# SensorStick.net
KiCad netlist of a schematic drawn in EAGLE
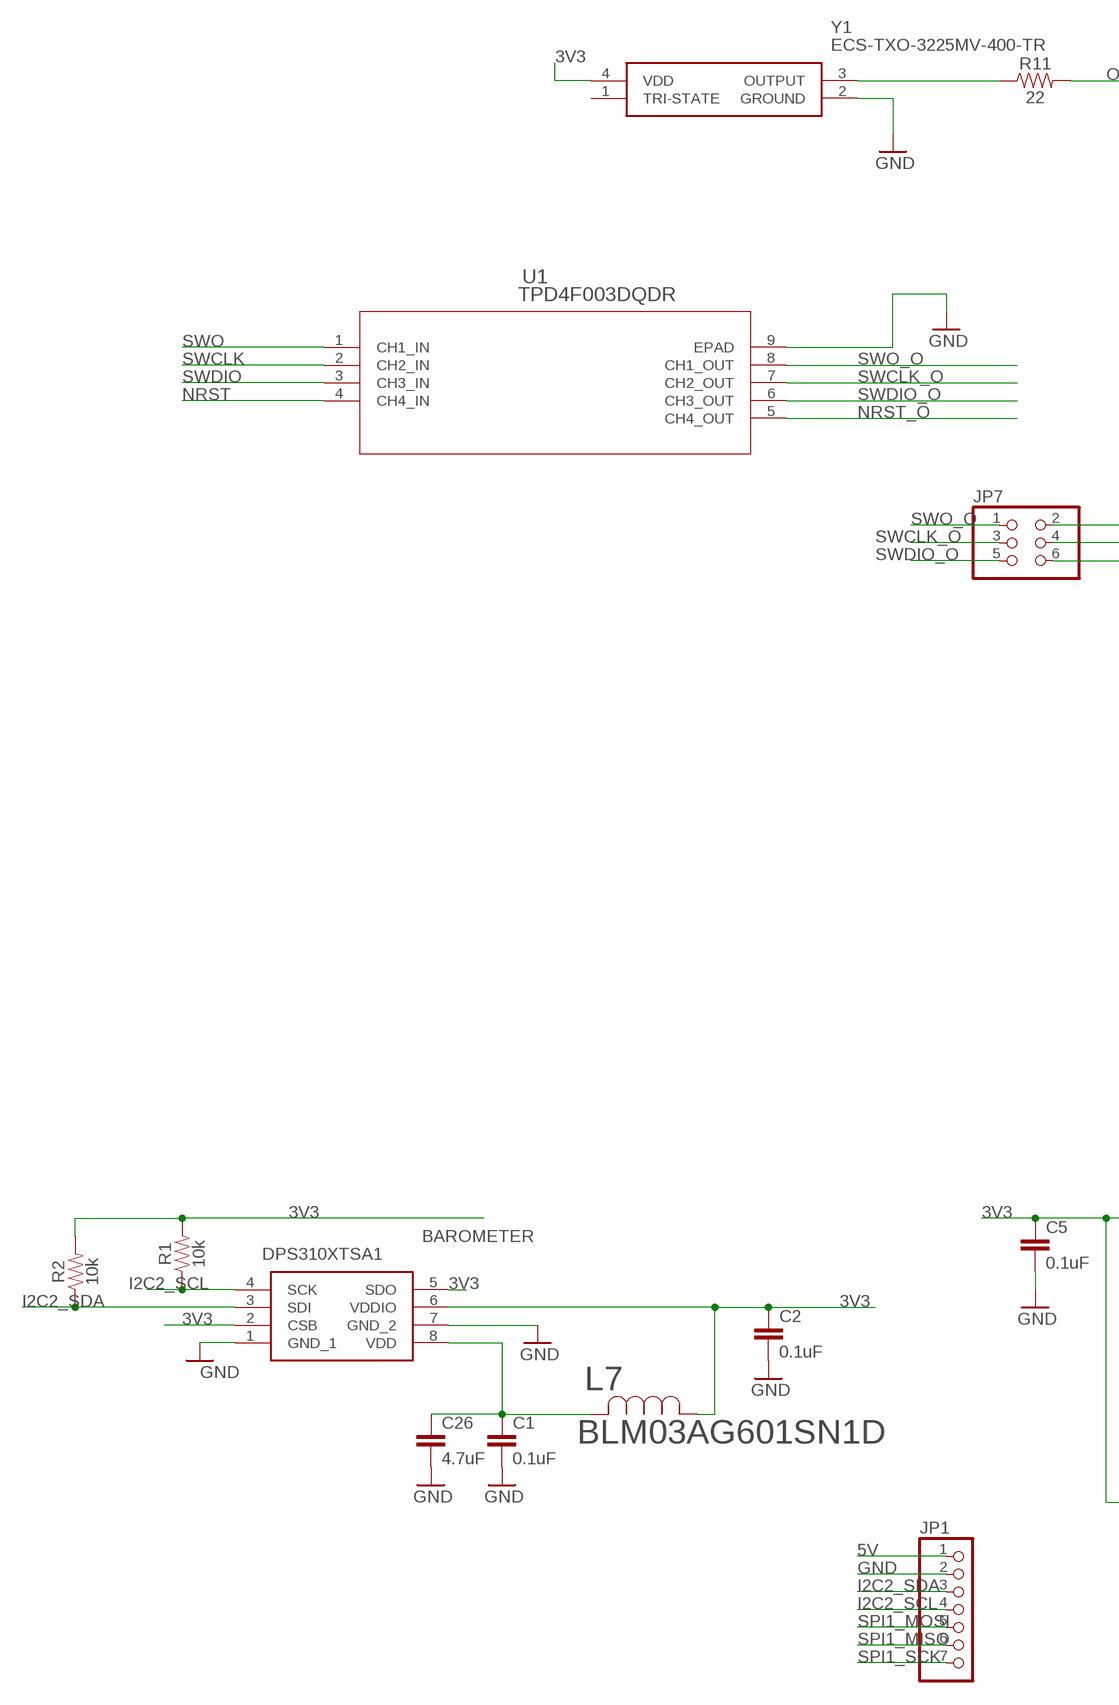
[diagram p0: schematic, sheet 1, part 1 of 2]
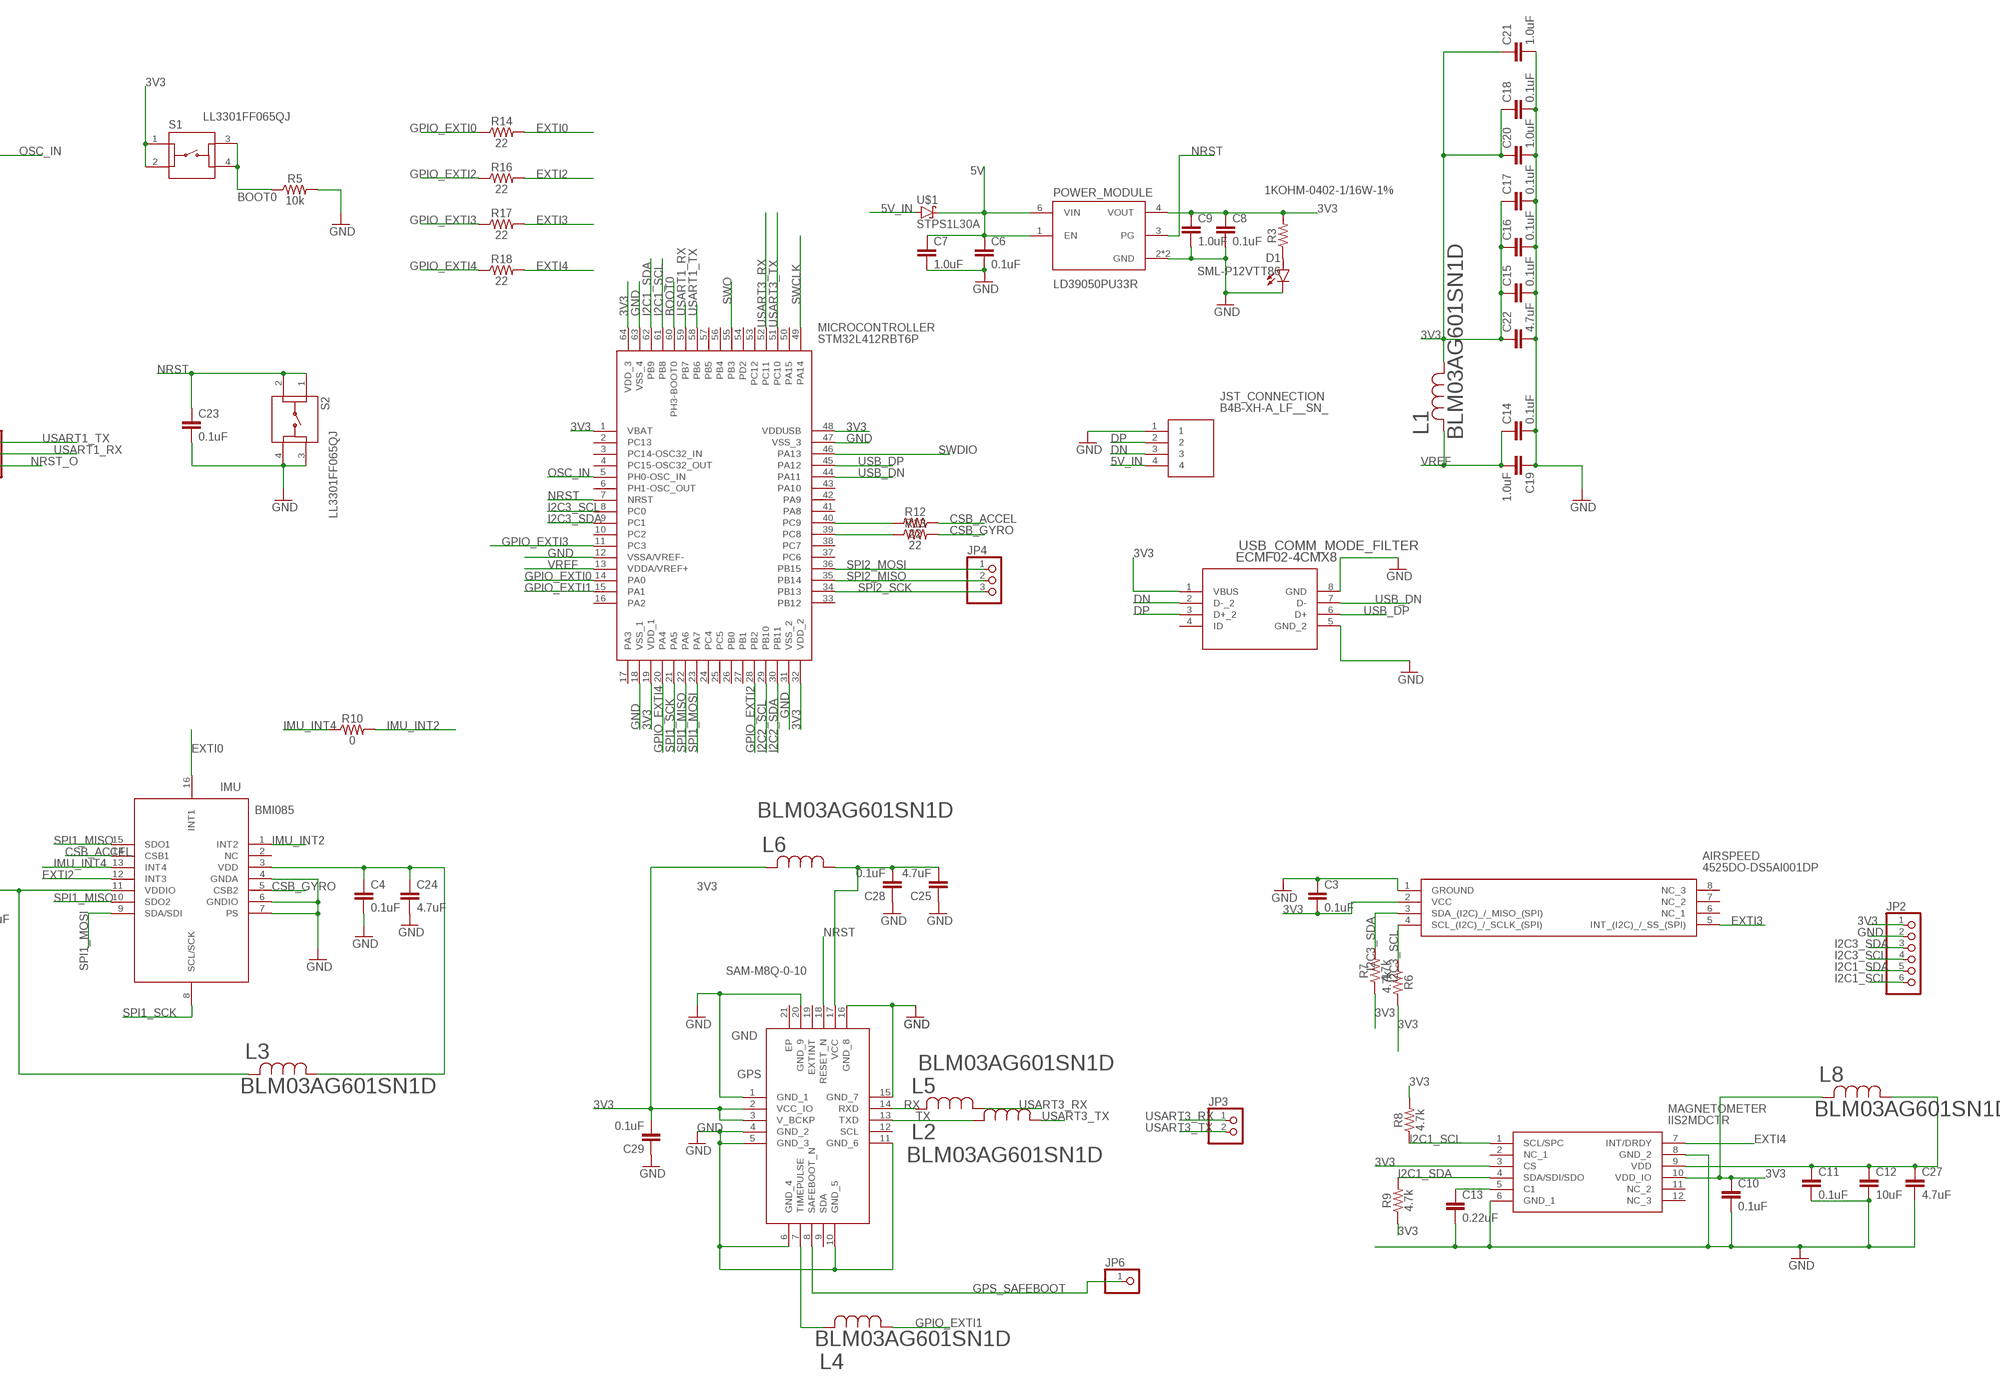
[diagram p1: schematic, sheet 1, part 2 of 2]

(export (version "E")
  (design (tool "Eeschema 10.0.6"))
  (components
    (comp (ref "AIRSPEED")
      (value "4525DO-DS5AI001DP")
      (footprint "eagle-import:4525DO-DS...P")
      (fields (field (name "MOUSER_PART_NUMBER") "824-4525DODS5AI001DP"))
      (libsource (lib "eagle-import") (part "4525DO-DS5AI001DP"))
    )
    (comp (ref "BAROMETER")
      (value "DPS310XTSA1")
      (footprint "eagle-import:DPS310XTSA1")
      (fields (field (name "MOUSER_PART_NUMBER") "726-DPS310XTSA1"))
      (libsource (lib "eagle-import") (part "DPS310XTSA1"))
    )
    (comp (ref "C1")
      (value "0.1uF")
      (footprint "eagle-import:0402")
      (libsource (lib "eagle-import") (part "0.1UF-0402-6.3V-10%-X7R"))
    )
    (comp (ref "C2")
      (value "0.1uF")
      (footprint "eagle-import:0402")
      (libsource (lib "eagle-import") (part "0.1UF-0402-6.3V-10%-X7R"))
    )
    (comp (ref "C3")
      (value "0.1uF")
      (footprint "eagle-import:0402")
      (fields (field (name "SPICEPREFIX") "C"))
      (libsource (lib "eagle-import") (part "0.1UF-0402-6.3V-10%-X7R"))
    )
    (comp (ref "C4")
      (value "0.1uF")
      (footprint "eagle-import:0402")
      (libsource (lib "eagle-import") (part "0.1UF-0402-6.3V-10%-X7R"))
    )
    (comp (ref "C5")
      (value "0.1uF")
      (footprint "eagle-import:0402")
      (libsource (lib "eagle-import") (part "0.1UF-0402-6.3V-10%-X7R"))
    )
    (comp (ref "C6")
      (value "0.1uF")
      (footprint "eagle-import:0402")
      (libsource (lib "eagle-import") (part "0.1UF-0402-6.3V-10%-X7R"))
    )
    (comp (ref "C7")
      (value "1.0uF")
      (footprint "eagle-import:0402")
      (libsource (lib "eagle-import") (part "1.0UF-0402-16V-10%"))
    )
    (comp (ref "C8")
      (value "0.1uF")
      (footprint "eagle-import:0402")
      (libsource (lib "eagle-import") (part "0.1UF-0402-6.3V-10%-X7R"))
    )
    (comp (ref "C9")
      (value "1.0uF")
      (footprint "eagle-import:0402")
      (libsource (lib "eagle-import") (part "1.0UF-0402-16V-10%"))
    )
    (comp (ref "C10")
      (value "0.1uF")
      (footprint "eagle-import:0402")
      (libsource (lib "eagle-import") (part "0.1UF-0402-6.3V-10%-X7R"))
    )
    (comp (ref "C11")
      (value "0.1uF")
      (footprint "eagle-import:0402")
      (libsource (lib "eagle-import") (part "0.1UF-0402-6.3V-10%-X7R"))
    )
    (comp (ref "C12")
      (value "10uF")
      (footprint "eagle-import:0603")
      (libsource (lib "eagle-import") (part "10UF-0603-6.3V-20%"))
    )
    (comp (ref "C13")
      (value "0.22uF")
      (footprint "eagle-import:0603")
      (libsource (lib "eagle-import") (part "0.22UF-0603-25V-10%"))
    )
    (comp (ref "C14")
      (value "0.1uF")
      (footprint "eagle-import:0603")
      (libsource (lib "eagle-import") (part "SparkFun-Capacitors_510_0.1UF-0603-25V-5%"))
    )
    (comp (ref "C15")
      (value "0.1uF")
      (footprint "eagle-import:0603")
      (libsource (lib "eagle-import") (part "SparkFun-Capacitors_510_0.1UF-0603-25V-5%"))
    )
    (comp (ref "C16")
      (value "0.1uF")
      (footprint "eagle-import:0603")
      (libsource (lib "eagle-import") (part "SparkFun-Capacitors_510_0.1UF-0603-25V-5%"))
    )
    (comp (ref "C17")
      (value "0.1uF")
      (footprint "eagle-import:0603")
      (libsource (lib "eagle-import") (part "SparkFun-Capacitors_510_0.1UF-0603-25V-5%"))
    )
    (comp (ref "C18")
      (value "0.1uF")
      (footprint "eagle-import:0603")
      (libsource (lib "eagle-import") (part "SparkFun-Capacitors_510_0.1UF-0603-25V-5%"))
    )
    (comp (ref "C19")
      (value "1.0uF")
      (footprint "eagle-import:0805")
      (libsource (lib "eagle-import") (part "SparkFun-Capacitors_510_1.0UF-0805-25V-10%"))
    )
    (comp (ref "C20")
      (value "1.0uF")
      (footprint "eagle-import:0805")
      (libsource (lib "eagle-import") (part "SparkFun-Capacitors_510_1.0UF-0805-25V-10%"))
    )
    (comp (ref "C21")
      (value "1.0uF")
      (footprint "eagle-import:0805")
      (libsource (lib "eagle-import") (part "SparkFun-Capacitors_510_1.0UF-0805-25V-10%"))
    )
    (comp (ref "C22")
      (value "4.7uF")
      (footprint "eagle-import:0603")
      (libsource (lib "eagle-import") (part "4.7UF0603"))
    )
    (comp (ref "C23")
      (value "0.1uF")
      (footprint "eagle-import:0603")
      (libsource (lib "eagle-import") (part "SparkFun-Capacitors_510_0.1UF-0603-25V-5%"))
    )
    (comp (ref "C24")
      (value "4.7uF")
      (footprint "eagle-import:0603")
      (libsource (lib "eagle-import") (part "4.7UF0603"))
    )
    (comp (ref "C25")
      (value "4.7uF")
      (footprint "eagle-import:0603")
      (libsource (lib "eagle-import") (part "4.7UF0603"))
    )
    (comp (ref "C26")
      (value "4.7uF")
      (footprint "eagle-import:0603")
      (libsource (lib "eagle-import") (part "4.7UF0603"))
    )
    (comp (ref "C27")
      (value "4.7uF")
      (footprint "eagle-import:0603")
      (libsource (lib "eagle-import") (part "4.7UF0603"))
    )
    (comp (ref "C28")
      (value "0.1uF")
      (footprint "eagle-import:0402")
      (libsource (lib "eagle-import") (part "SparkFun-Capacitors_510_0.1UF-0402-16V-10%"))
    )
    (comp (ref "C29")
      (value "0.1uF")
      (footprint "eagle-import:0402")
      (libsource (lib "eagle-import") (part "SparkFun-Capacitors_510_0.1UF-0402-16V-10%"))
    )
    (comp (ref "D1")
      (value "SML-P12VTT86")
      (footprint "eagle-import:LED_SML-P11UTT86R")
      (fields (field (name "MF") "Rohm"))
      (libsource (lib "eagle-import") (part "SML-P12VTT86"))
    )
    (comp (ref "GPS")
      (value "SAM-M8Q-0-10")
      (footprint "eagle-import:SAMM8Q010")
      (libsource (lib "eagle-import") (part "SAM-M8Q-0-10"))
    )
    (comp (ref "IMU")
      (value "BMI085")
      (footprint "eagle-import:BMI085")
      (fields (field (name "MOUSER_PART_NUMBER") "262-BMI085"))
      (libsource (lib "eagle-import") (part "BMI085"))
    )
    (comp (ref "JP1")
      (value "PINHD-1X7")
      (footprint "eagle-import:1X07")
      (libsource (lib "eagle-import") (part "PINHD-1X7"))
    )
    (comp (ref "JP2")
      (value "PINHD-1X6")
      (footprint "eagle-import:1X06")
      (libsource (lib "eagle-import") (part "PINHD-1X6"))
    )
    (comp (ref "JP3")
      (value "PINHD-1X2")
      (footprint "eagle-import:1X02")
      (libsource (lib "eagle-import") (part "PINHD-1X2"))
    )
    (comp (ref "JP4")
      (value "PINHD-1X3")
      (footprint "eagle-import:1X03")
      (libsource (lib "eagle-import") (part "PINHD-1X3"))
    )
    (comp (ref "JP6")
      (value "PINHD-1X1")
      (footprint "eagle-import:1X01")
      (libsource (lib "eagle-import") (part "PINHD-1X1"))
    )
    (comp (ref "JP7")
      (value "PINHD-2X3")
      (footprint "eagle-import:2X03")
      (libsource (lib "eagle-import") (part "PINHD-2X3"))
    )
    (comp (ref "JST_CONNECTION")
      (value "B4B-XH-A_LF__SN_")
      (footprint "eagle-import:B4BXHALFSN")
      (fields (field (name "ARROW_PART_NUMBER") "B4B-XH-A(LF)(SN)"))
      (libsource (lib "eagle-import") (part "B4B-XH-A_LF__SN_"))
    )
    (comp (ref "L1")
      (value "BLM03AG601SN1D")
      (footprint "eagle-import:IND_BLM03_0201_MUR")
      (fields (field (name "COPYRIGHT") "Copyright (C) 2023 Ultra Librarian. All rights reserved."))
      (libsource (lib "eagle-import") (part "BLM03AG601SN1D"))
    )
    (comp (ref "L2")
      (value "BLM03AG601SN1D")
      (footprint "eagle-import:IND_BLM03_0201_MUR")
      (fields (field (name "COPYRIGHT") "Copyright (C) 2023 Ultra Librarian. All rights reserved."))
      (libsource (lib "eagle-import") (part "BLM03AG601SN1D"))
    )
    (comp (ref "L3")
      (value "BLM03AG601SN1D")
      (footprint "eagle-import:IND_BLM03_0201_MUR")
      (fields (field (name "COPYRIGHT") "Copyright (C) 2023 Ultra Librarian. All rights reserved."))
      (libsource (lib "eagle-import") (part "BLM03AG601SN1D"))
    )
    (comp (ref "L4")
      (value "BLM03AG601SN1D")
      (footprint "eagle-import:IND_BLM03_0201_MUR")
      (fields (field (name "COPYRIGHT") "Copyright (C) 2023 Ultra Librarian. All rights reserved."))
      (libsource (lib "eagle-import") (part "BLM03AG601SN1D"))
    )
    (comp (ref "L5")
      (value "BLM03AG601SN1D")
      (footprint "eagle-import:IND_BLM03_0201_MUR")
      (fields (field (name "COPYRIGHT") "Copyright (C) 2023 Ultra Librarian. All rights reserved."))
      (libsource (lib "eagle-import") (part "BLM03AG601SN1D"))
    )
    (comp (ref "L6")
      (value "BLM03AG601SN1D")
      (footprint "eagle-import:IND_BLM03_0201_MUR")
      (fields (field (name "COPYRIGHT") "Copyright (C) 2023 Ultra Librarian. All rights reserved."))
      (libsource (lib "eagle-import") (part "BLM03AG601SN1D"))
    )
    (comp (ref "L7")
      (value "BLM03AG601SN1D")
      (footprint "eagle-import:IND_BLM03_0201_MUR")
      (fields (field (name "COPYRIGHT") "Copyright (C) 2023 Ultra Librarian. All rights reserved."))
      (libsource (lib "eagle-import") (part "BLM03AG601SN1D"))
    )
    (comp (ref "L8")
      (value "BLM03AG601SN1D")
      (footprint "eagle-import:IND_BLM03_0201_MUR")
      (fields (field (name "COPYRIGHT") "Copyright (C) 2023 Ultra Librarian. All rights reserved."))
      (libsource (lib "eagle-import") (part "BLM03AG601SN1D"))
    )
    (comp (ref "MAGNETOMETER")
      (value "IIS2MDCTR")
      (footprint "eagle-import:IIS2MDCTR")
      (fields (field (name "MOUSER_PART_NUMBER") "511-IIS2MDCTR"))
      (libsource (lib "eagle-import") (part "IIS2MDCTR"))
    )
    (comp (ref "MICROCONTROLLER")
      (value "STM32L412RBT6P")
      (footprint "eagle-import:QFP50P1200X1200X160-64N")
      (fields (field (name "MOUSER_PART_NUMBER") "511-STM32L412RBT6P"))
      (libsource (lib "eagle-import") (part "STM32L412RBT6P"))
    )
    (comp (ref "POWER_MODULE")
      (value "LD39050PU33R")
      (footprint "eagle-import:SON95P300X300X100-7N")
      (fields (field (name "MF") "STMicroelectronics"))
      (libsource (lib "eagle-import") (part "LD39050PU33R"))
    )
    (comp (ref "R1")
      (value "10k")
      (footprint "eagle-import:0402")
      (libsource (lib "eagle-import") (part "10KOHM-0402-1/16W-1%"))
    )
    (comp (ref "R2")
      (value "10k")
      (footprint "eagle-import:0402")
      (libsource (lib "eagle-import") (part "10KOHM-0402-1/16W-1%"))
    )
    (comp (ref "R3")
      (value "1KOHM-0402-1/16W-1%")
      (footprint "eagle-import:0402")
      (libsource (lib "eagle-import") (part "1KOHM-0402-1/16W-1%"))
    )
    (comp (ref "R5")
      (value "10k")
      (footprint "eagle-import:0603")
      (libsource (lib "eagle-import") (part "SparkFun-Resistors_532_10KOHM-0603-1/10W-1%"))
    )
    (comp (ref "R6")
      (value "4.7k")
      (footprint "eagle-import:0603")
      (libsource (lib "eagle-import") (part "4.7KOHM-0603-1/10W-1%"))
    )
    (comp (ref "R7")
      (value "4.7k")
      (footprint "eagle-import:0603")
      (libsource (lib "eagle-import") (part "4.7KOHM-0603-1/10W-1%"))
    )
    (comp (ref "R8")
      (value "4.7k")
      (footprint "eagle-import:0603")
      (libsource (lib "eagle-import") (part "4.7KOHM-0603-1/10W-1%"))
    )
    (comp (ref "R9")
      (value "4.7k")
      (footprint "eagle-import:0603")
      (libsource (lib "eagle-import") (part "4.7KOHM-0603-1/10W-1%"))
    )
    (comp (ref "R10")
      (value "0")
      (footprint "eagle-import:0603")
      (libsource (lib "eagle-import") (part "0OHM-0603-1/10W-5%"))
    )
    (comp (ref "R11")
      (value "22")
      (footprint "eagle-import:0402")
      (libsource (lib "eagle-import") (part "22OHM-0402-1/10W-1%"))
    )
    (comp (ref "R12")
      (value "22")
      (footprint "eagle-import:0402")
      (libsource (lib "eagle-import") (part "22OHM-0402-1/10W-1%"))
    )
    (comp (ref "R13")
      (value "22")
      (footprint "eagle-import:0402")
      (libsource (lib "eagle-import") (part "22OHM-0402-1/10W-1%"))
    )
    (comp (ref "R14")
      (value "22")
      (footprint "eagle-import:0402")
      (libsource (lib "eagle-import") (part "22OHM-0402-1/10W-1%"))
    )
    (comp (ref "R16")
      (value "22")
      (footprint "eagle-import:0402")
      (libsource (lib "eagle-import") (part "22OHM-0402-1/10W-1%"))
    )
    (comp (ref "R17")
      (value "22")
      (footprint "eagle-import:0402")
      (libsource (lib "eagle-import") (part "22OHM-0402-1/10W-1%"))
    )
    (comp (ref "R18")
      (value "22")
      (footprint "eagle-import:0402")
      (libsource (lib "eagle-import") (part "22OHM-0402-1/10W-1%"))
    )
    (comp (ref "S1")
      (value "LL3301FF065QJ")
      (footprint "eagle-import:LL3301FF065QJ")
      (fields (field (name "MOUSER_PART_NUMBER") "612-LL3301FF065QJ"))
      (libsource (lib "eagle-import") (part "LL3301FF065QJ"))
    )
    (comp (ref "S2")
      (value "LL3301FF065QJ")
      (footprint "eagle-import:LL3301FF065QJ")
      (fields (field (name "MOUSER_PART_NUMBER") "612-LL3301FF065QJ"))
      (libsource (lib "eagle-import") (part "LL3301FF065QJ"))
    )
    (comp (ref "U$1")
      (value "STPS1L30A")
      (footprint "eagle-import:DIOM5226X223N")
      (libsource (lib "eagle-import") (part "STPS1L30A"))
    )
    (comp (ref "U1")
      (value "TPD4F003DQDR")
      (footprint "eagle-import:DQD8_1P2X0P4")
      (fields (field (name "COPYRIGHT") "Copyright (C) 2023 Ultra Librarian. All rights reserved."))
      (libsource (lib "eagle-import") (part "TPD4F003DQDR"))
    )
    (comp (ref "USB_COMM_MODE_FILTER")
      (value "ECMF02-4CMX8")
      (footprint "eagle-import:MICRO_QFN-8L_STM")
      (fields (field (name "COPYRIGHT") "Copyright (C) 2023 Ultra Librarian. All rights reserved."))
      (libsource (lib "eagle-import") (part "ECMF02-4CMX8"))
    )
    (comp (ref "Y1")
      (value "ECS-TXO-3225MV-400-TR")
      (footprint "eagle-import:ECSTXO3225MV400TR")
      (libsource (lib "eagle-import") (part "ECS-TXO-3225MV-400-TR"))
    )
  )
  (nets
    (net (code "1") (name "/3V3") (class "Default")
      (node (ref "AIRSPEED") (pin "2") (pinfunction "VCC_2") (pintype "power_in"))
      (node (ref "BAROMETER") (pin "2") (pinfunction "CSB_2") (pintype "bidirectional"))
      (node (ref "BAROMETER") (pin "5") (pinfunction "SDO_5") (pintype "bidirectional"))
      (node (ref "BAROMETER") (pin "6") (pinfunction "VDDIO_6") (pintype "bidirectional"))
      (node (ref "C10") (pin "1") (pinfunction "1_1") (pintype "passive"))
      (node (ref "C15") (pin "1") (pinfunction "1_1") (pintype "passive"))
      (node (ref "C16") (pin "1") (pinfunction "1_1") (pintype "passive"))
      (node (ref "C17") (pin "1") (pinfunction "1_1") (pintype "passive"))
      (node (ref "C18") (pin "1") (pinfunction "1_1") (pintype "passive"))
      (node (ref "C2") (pin "1") (pinfunction "1_1") (pintype "passive"))
      (node (ref "C20") (pin "1") (pinfunction "1_1") (pintype "passive"))
      (node (ref "C21") (pin "1") (pinfunction "1_1") (pintype "passive"))
      (node (ref "C22") (pin "1") (pinfunction "1_1") (pintype "passive"))
      (node (ref "C29") (pin "2") (pinfunction "2_2") (pintype "passive"))
      (node (ref "C3") (pin "2") (pinfunction "2_2") (pintype "passive"))
      (node (ref "C5") (pin "1") (pinfunction "1_1") (pintype "passive"))
      (node (ref "C8") (pin "1") (pinfunction "1_1") (pintype "passive"))
      (node (ref "C9") (pin "1") (pinfunction "1_1") (pintype "passive"))
      (node (ref "GPS") (pin "2") (pinfunction "VCC_IO_2") (pintype "bidirectional"))
      (node (ref "GPS") (pin "3") (pinfunction "V_BCKP_3") (pintype "bidirectional"))
      (node (ref "IMU") (pin "11") (pinfunction "VDDIO_11") (pintype "bidirectional"))
      (node (ref "JP2") (pin "1") (pinfunction "1_1") (pintype "passive"))
      (node (ref "L1") (pin "1") (pinfunction "1_1") (pintype "passive"))
      (node (ref "L3") (pin "2") (pinfunction "2_2") (pintype "passive"))
      (node (ref "L6") (pin "2") (pinfunction "2_2") (pintype "passive"))
      (node (ref "L7") (pin "1") (pinfunction "1_1") (pintype "passive"))
      (node (ref "L8") (pin "2") (pinfunction "2_2") (pintype "passive"))
      (node (ref "MAGNETOMETER") (pin "10") (pinfunction "VDD_IO_10") (pintype "bidirectional"))
      (node (ref "MAGNETOMETER") (pin "3") (pinfunction "CS_3") (pintype "bidirectional"))
      (node (ref "MICROCONTROLLER") (pin "1") (pinfunction "VBAT_1") (pintype "bidirectional"))
      (node (ref "MICROCONTROLLER") (pin "19") (pinfunction "VDD_1_19") (pintype "bidirectional"))
      (node (ref "MICROCONTROLLER") (pin "32") (pinfunction "VDD_2_32") (pintype "bidirectional"))
      (node (ref "MICROCONTROLLER") (pin "48") (pinfunction "VDDUSB_48") (pintype "bidirectional"))
      (node (ref "MICROCONTROLLER") (pin "64") (pinfunction "VDD_3_64") (pintype "bidirectional"))
      (node (ref "POWER_MODULE") (pin "4") (pinfunction "VOUT_4") (pintype "output"))
      (node (ref "R1") (pin "2") (pinfunction "2_2") (pintype "passive"))
      (node (ref "R2") (pin "2") (pinfunction "2_2") (pintype "passive"))
      (node (ref "R3") (pin "2") (pinfunction "2_2") (pintype "passive"))
      (node (ref "R6") (pin "2") (pinfunction "2_2") (pintype "passive"))
      (node (ref "R7") (pin "1") (pinfunction "1_1") (pintype "passive"))
      (node (ref "R8") (pin "2") (pinfunction "2_2") (pintype "passive"))
      (node (ref "R9") (pin "1") (pinfunction "1_1") (pintype "passive"))
      (node (ref "S1") (pin "1") (pinfunction "1_1") (pintype "passive"))
      (node (ref "S1") (pin "2") (pinfunction "2_2") (pintype "passive"))
      (node (ref "USB_COMM_MODE_FILTER") (pin "1") (pinfunction "VBUS_1") (pintype "power_in"))
      (node (ref "Y1") (pin "4") (pinfunction "VDD_4") (pintype "bidirectional"))
    )
    (net (code "2") (name "/5V") (class "Default")
      (node (ref "C6") (pin "1") (pinfunction "1_1") (pintype "passive"))
      (node (ref "C7") (pin "1") (pinfunction "1_1") (pintype "passive"))
      (node (ref "JP1") (pin "1") (pinfunction "1_1") (pintype "passive"))
      (node (ref "POWER_MODULE") (pin "1") (pinfunction "EN_1") (pintype "input"))
      (node (ref "POWER_MODULE") (pin "6") (pinfunction "VIN_6") (pintype "power_in"))
      (node (ref "U$1") (pin "1") (pinfunction "C_1") (pintype "passive"))
    )
    (net (code "3") (name "/5V_IN") (class "Default")
      (node (ref "JST_CONNECTION") (pin "4") (pinfunction "4_4") (pintype "bidirectional"))
      (node (ref "U$1") (pin "2") (pinfunction "A_2") (pintype "passive"))
    )
    (net (code "4") (name "/BOOT0") (class "Default")
      (node (ref "MICROCONTROLLER") (pin "60") (pinfunction "PH3-BOOT0_60") (pintype "bidirectional"))
      (node (ref "R5") (pin "1") (pinfunction "1_1") (pintype "passive"))
      (node (ref "S1") (pin "3") (pinfunction "3_3") (pintype "passive"))
      (node (ref "S1") (pin "4") (pinfunction "4_4") (pintype "passive"))
    )
    (net (code "5") (name "/CSB_ACCEL") (class "Default")
      (node (ref "IMU") (pin "14") (pinfunction "CSB1_14") (pintype "bidirectional"))
      (node (ref "R12") (pin "2") (pinfunction "2_2") (pintype "passive"))
    )
    (net (code "6") (name "/CSB_GYRO") (class "Default")
      (node (ref "IMU") (pin "5") (pinfunction "CSB2_5") (pintype "bidirectional"))
      (node (ref "R13") (pin "2") (pinfunction "2_2") (pintype "passive"))
    )
    (net (code "7") (name "/DN") (class "Default")
      (node (ref "JST_CONNECTION") (pin "3") (pinfunction "3_3") (pintype "bidirectional"))
      (node (ref "USB_COMM_MODE_FILTER") (pin "2") (pinfunction "D-_2_2") (pintype "bidirectional"))
    )
    (net (code "8") (name "/DP") (class "Default")
      (node (ref "JST_CONNECTION") (pin "2") (pinfunction "2_2") (pintype "bidirectional"))
      (node (ref "USB_COMM_MODE_FILTER") (pin "3") (pinfunction "D+_2_3") (pintype "bidirectional"))
    )
    (net (code "9") (name "/EXTI0") (class "Default")
      (node (ref "IMU") (pin "16") (pinfunction "INT1_16") (pintype "bidirectional"))
      (node (ref "R14") (pin "2") (pinfunction "2_2") (pintype "passive"))
    )
    (net (code "10") (name "/EXTI2") (class "Default")
      (node (ref "IMU") (pin "12") (pinfunction "INT3_12") (pintype "bidirectional"))
      (node (ref "R16") (pin "2") (pinfunction "2_2") (pintype "passive"))
    )
    (net (code "11") (name "/EXTI3") (class "Default")
      (node (ref "AIRSPEED") (pin "5") (pinfunction "INT_(I2C)_/_SS_(SPI)_5") (pintype "bidirectional"))
      (node (ref "R17") (pin "2") (pinfunction "2_2") (pintype "passive"))
    )
    (net (code "12") (name "/EXTI4") (class "Default")
      (node (ref "MAGNETOMETER") (pin "7") (pinfunction "INT/DRDY_7") (pintype "bidirectional"))
      (node (ref "R18") (pin "2") (pinfunction "2_2") (pintype "passive"))
    )
    (net (code "13") (name "/GPIO_EXTI0") (class "Default")
      (node (ref "MICROCONTROLLER") (pin "14") (pinfunction "PA0_14") (pintype "bidirectional"))
      (node (ref "R14") (pin "1") (pinfunction "1_1") (pintype "passive"))
    )
    (net (code "14") (name "/GPIO_EXTI1") (class "Default")
      (node (ref "L4") (pin "1") (pinfunction "1_1") (pintype "passive"))
      (node (ref "MICROCONTROLLER") (pin "15") (pinfunction "PA1_15") (pintype "bidirectional"))
    )
    (net (code "15") (name "/GPIO_EXTI2") (class "Default")
      (node (ref "MICROCONTROLLER") (pin "28") (pinfunction "PB2_28") (pintype "bidirectional"))
      (node (ref "R16") (pin "1") (pinfunction "1_1") (pintype "passive"))
    )
    (net (code "16") (name "/GPIO_EXTI3") (class "Default")
      (node (ref "MICROCONTROLLER") (pin "11") (pinfunction "PC3_11") (pintype "bidirectional"))
      (node (ref "R17") (pin "1") (pinfunction "1_1") (pintype "passive"))
    )
    (net (code "17") (name "/GPIO_EXTI4") (class "Default")
      (node (ref "MICROCONTROLLER") (pin "20") (pinfunction "PA4_20") (pintype "bidirectional"))
      (node (ref "R18") (pin "1") (pinfunction "1_1") (pintype "passive"))
    )
    (net (code "18") (name "/GPS_SAFEBOOT") (class "Default")
      (node (ref "GPS") (pin "8") (pinfunction "SAFEBOOT_N_8") (pintype "bidirectional"))
      (node (ref "JP6") (pin "1") (pinfunction "1_1") (pintype "passive"))
    )
    (net (code "19") (name "/I2C1_SCL") (class "Default")
      (node (ref "JP2") (pin "6") (pinfunction "6_6") (pintype "passive"))
      (node (ref "MAGNETOMETER") (pin "1") (pinfunction "SCL/SPC_1") (pintype "bidirectional"))
      (node (ref "MICROCONTROLLER") (pin "61") (pinfunction "PB8_61") (pintype "bidirectional"))
      (node (ref "R8") (pin "1") (pinfunction "1_1") (pintype "passive"))
    )
    (net (code "20") (name "/I2C1_SDA") (class "Default")
      (node (ref "JP2") (pin "5") (pinfunction "5_5") (pintype "passive"))
      (node (ref "MAGNETOMETER") (pin "4") (pinfunction "SDA/SDI/SDO_4") (pintype "bidirectional"))
      (node (ref "MICROCONTROLLER") (pin "62") (pinfunction "PB9_62") (pintype "bidirectional"))
      (node (ref "R9") (pin "2") (pinfunction "2_2") (pintype "passive"))
    )
    (net (code "21") (name "/I2C2_SCL") (class "Default")
      (node (ref "BAROMETER") (pin "4") (pinfunction "SCK_4") (pintype "bidirectional"))
      (node (ref "JP1") (pin "4") (pinfunction "4_4") (pintype "passive"))
      (node (ref "MICROCONTROLLER") (pin "29") (pinfunction "PB10_29") (pintype "bidirectional"))
      (node (ref "R1") (pin "1") (pinfunction "1_1") (pintype "passive"))
    )
    (net (code "22") (name "/I2C2_SDA") (class "Default")
      (node (ref "BAROMETER") (pin "3") (pinfunction "SDI_3") (pintype "bidirectional"))
      (node (ref "JP1") (pin "3") (pinfunction "3_3") (pintype "passive"))
      (node (ref "MICROCONTROLLER") (pin "30") (pinfunction "PB11_30") (pintype "bidirectional"))
      (node (ref "R2") (pin "1") (pinfunction "1_1") (pintype "passive"))
    )
    (net (code "23") (name "/I2C3_SCL") (class "Default")
      (node (ref "AIRSPEED") (pin "4") (pinfunction "SCL_(I2C)_/_SCLK_(SPI)_4") (pintype "bidirectional"))
      (node (ref "JP2") (pin "4") (pinfunction "4_4") (pintype "passive"))
      (node (ref "MICROCONTROLLER") (pin "8") (pinfunction "PC0_8") (pintype "bidirectional"))
      (node (ref "R6") (pin "1") (pinfunction "1_1") (pintype "passive"))
    )
    (net (code "24") (name "/I2C3_SDA") (class "Default")
      (node (ref "AIRSPEED") (pin "3") (pinfunction "SDA_(I2C)_/_MISO_(SPI)_3") (pintype "bidirectional"))
      (node (ref "JP2") (pin "3") (pinfunction "3_3") (pintype "passive"))
      (node (ref "MICROCONTROLLER") (pin "9") (pinfunction "PC1_9") (pintype "bidirectional"))
      (node (ref "R7") (pin "2") (pinfunction "2_2") (pintype "passive"))
    )
    (net (code "25") (name "/IMU_INT2") (class "Default")
      (node (ref "IMU") (pin "1") (pinfunction "INT2_1") (pintype "bidirectional"))
      (node (ref "R10") (pin "2") (pinfunction "2_2") (pintype "passive"))
    )
    (net (code "26") (name "/IMU_INT4") (class "Default")
      (node (ref "IMU") (pin "13") (pinfunction "INT4_13") (pintype "bidirectional"))
      (node (ref "R10") (pin "1") (pinfunction "1_1") (pintype "passive"))
    )
    (net (code "27") (name "/NRST") (class "Default")
      (node (ref "C23") (pin "1") (pinfunction "1_1") (pintype "passive"))
      (node (ref "GPS") (pin "18") (pinfunction "RESET_N_18") (pintype "bidirectional"))
      (node (ref "MICROCONTROLLER") (pin "7") (pinfunction "NRST_7") (pintype "bidirectional"))
      (node (ref "POWER_MODULE") (pin "3") (pinfunction "PG_3") (pintype "bidirectional"))
      (node (ref "S2") (pin "1") (pinfunction "1_1") (pintype "passive"))
      (node (ref "S2") (pin "2") (pinfunction "2_2") (pintype "passive"))
      (node (ref "U1") (pin "4") (pinfunction "CH4_IN_4") (pintype "input"))
    )
    (net (code "28") (name "/NRST_O") (class "Default")
      (node (ref "JP7") (pin "6") (pinfunction "6_6") (pintype "passive"))
      (node (ref "U1") (pin "5") (pinfunction "CH4_OUT_5") (pintype "output"))
    )
    (net (code "29") (name "/OSC_IN") (class "Default")
      (node (ref "MICROCONTROLLER") (pin "5") (pinfunction "PH0-OSC_IN_5") (pintype "bidirectional"))
      (node (ref "R11") (pin "2") (pinfunction "2_2") (pintype "passive"))
    )
    (net (code "30") (name "/RX") (class "Default")
      (node (ref "GPS") (pin "14") (pinfunction "RXD_14") (pintype "bidirectional"))
      (node (ref "L5") (pin "2") (pinfunction "2_2") (pintype "passive"))
    )
    (net (code "31") (name "/SPI1_MISO") (class "Default")
      (node (ref "IMU") (pin "10") (pinfunction "SDO2_10") (pintype "bidirectional"))
      (node (ref "IMU") (pin "15") (pinfunction "SDO1_15") (pintype "bidirectional"))
      (node (ref "JP1") (pin "6") (pinfunction "6_6") (pintype "passive"))
      (node (ref "MICROCONTROLLER") (pin "22") (pinfunction "PA6_22") (pintype "bidirectional"))
    )
    (net (code "32") (name "/SPI1_MOSI") (class "Default")
      (node (ref "IMU") (pin "9") (pinfunction "SDA/SDI_9") (pintype "bidirectional"))
      (node (ref "JP1") (pin "5") (pinfunction "5_5") (pintype "passive"))
      (node (ref "MICROCONTROLLER") (pin "23") (pinfunction "PA7_23") (pintype "bidirectional"))
    )
    (net (code "33") (name "/SPI1_SCK") (class "Default")
      (node (ref "IMU") (pin "8") (pinfunction "SCL/SCK_8") (pintype "bidirectional"))
      (node (ref "JP1") (pin "7") (pinfunction "7_7") (pintype "passive"))
      (node (ref "MICROCONTROLLER") (pin "21") (pinfunction "PA5_21") (pintype "bidirectional"))
    )
    (net (code "34") (name "/SPI2_MISO") (class "Default")
      (node (ref "JP4") (pin "2") (pinfunction "2_2") (pintype "passive"))
      (node (ref "MICROCONTROLLER") (pin "35") (pinfunction "PB14_35") (pintype "bidirectional"))
    )
    (net (code "35") (name "/SPI2_MOSI") (class "Default")
      (node (ref "JP4") (pin "1") (pinfunction "1_1") (pintype "passive"))
      (node (ref "MICROCONTROLLER") (pin "36") (pinfunction "PB15_36") (pintype "bidirectional"))
    )
    (net (code "36") (name "/SPI2_SCK") (class "Default")
      (node (ref "JP4") (pin "3") (pinfunction "3_3") (pintype "passive"))
      (node (ref "MICROCONTROLLER") (pin "34") (pinfunction "PB13_34") (pintype "bidirectional"))
    )
    (net (code "37") (name "/SWCLK") (class "Default")
      (node (ref "MICROCONTROLLER") (pin "49") (pinfunction "PA14_49") (pintype "bidirectional"))
      (node (ref "U1") (pin "2") (pinfunction "CH2_IN_2") (pintype "input"))
    )
    (net (code "38") (name "/SWCLK_O") (class "Default")
      (node (ref "JP7") (pin "3") (pinfunction "3_3") (pintype "passive"))
      (node (ref "U1") (pin "7") (pinfunction "CH2_OUT_7") (pintype "output"))
    )
    (net (code "39") (name "/SWDIO") (class "Default")
      (node (ref "MICROCONTROLLER") (pin "46") (pinfunction "PA13_46") (pintype "bidirectional"))
      (node (ref "U1") (pin "3") (pinfunction "CH3_IN_3") (pintype "input"))
    )
    (net (code "40") (name "/SWDIO_O") (class "Default")
      (node (ref "JP7") (pin "5") (pinfunction "5_5") (pintype "passive"))
      (node (ref "U1") (pin "6") (pinfunction "CH3_OUT_6") (pintype "output"))
    )
    (net (code "41") (name "/SWO") (class "Default")
      (node (ref "MICROCONTROLLER") (pin "55") (pinfunction "PB3_55") (pintype "bidirectional"))
      (node (ref "U1") (pin "1") (pinfunction "CH1_IN_1") (pintype "input"))
    )
    (net (code "42") (name "/SWO_O") (class "Default")
      (node (ref "JP7") (pin "1") (pinfunction "1_1") (pintype "passive"))
      (node (ref "U1") (pin "8") (pinfunction "CH1_OUT_8") (pintype "output"))
    )
    (net (code "43") (name "/TX") (class "Default")
      (node (ref "GPS") (pin "13") (pinfunction "TXD_13") (pintype "bidirectional"))
      (node (ref "L2") (pin "2") (pinfunction "2_2") (pintype "passive"))
    )
    (net (code "44") (name "/USART1_RX") (class "Default")
      (node (ref "JP7") (pin "4") (pinfunction "4_4") (pintype "passive"))
      (node (ref "MICROCONTROLLER") (pin "59") (pinfunction "PB7_59") (pintype "bidirectional"))
    )
    (net (code "45") (name "/USART1_TX") (class "Default")
      (node (ref "JP7") (pin "2") (pinfunction "2_2") (pintype "passive"))
      (node (ref "MICROCONTROLLER") (pin "58") (pinfunction "PB6_58") (pintype "bidirectional"))
    )
    (net (code "46") (name "/USART3_RX") (class "Default")
      (node (ref "JP3") (pin "1") (pinfunction "1_1") (pintype "passive"))
      (node (ref "L5") (pin "1") (pinfunction "1_1") (pintype "passive"))
      (node (ref "MICROCONTROLLER") (pin "52") (pinfunction "PC11_52") (pintype "bidirectional"))
    )
    (net (code "47") (name "/USART3_TX") (class "Default")
      (node (ref "JP3") (pin "2") (pinfunction "2_2") (pintype "passive"))
      (node (ref "L2") (pin "1") (pinfunction "1_1") (pintype "passive"))
      (node (ref "MICROCONTROLLER") (pin "51") (pinfunction "PC10_51") (pintype "bidirectional"))
    )
    (net (code "48") (name "/USB_DN") (class "Default")
      (node (ref "MICROCONTROLLER") (pin "44") (pinfunction "PA11_44") (pintype "bidirectional"))
      (node (ref "USB_COMM_MODE_FILTER") (pin "7") (pinfunction "D-_7") (pintype "bidirectional"))
    )
    (net (code "49") (name "/USB_DP") (class "Default")
      (node (ref "MICROCONTROLLER") (pin "45") (pinfunction "PA12_45") (pintype "bidirectional"))
      (node (ref "USB_COMM_MODE_FILTER") (pin "6") (pinfunction "D+_6") (pintype "bidirectional"))
    )
    (net (code "50") (name "/VREF") (class "Default")
      (node (ref "C14") (pin "1") (pinfunction "1_1") (pintype "passive"))
      (node (ref "C19") (pin "2") (pinfunction "2_2") (pintype "passive"))
      (node (ref "L1") (pin "2") (pinfunction "2_2") (pintype "passive"))
      (node (ref "MICROCONTROLLER") (pin "13") (pinfunction "VDDA/VREF+_13") (pintype "bidirectional"))
    )
    (net (code "51") (name "GND") (class "Default")
      (node (ref "AIRSPEED") (pin "1") (pinfunction "GROUND_1") (pintype "power_in"))
      (node (ref "BAROMETER") (pin "1") (pinfunction "GND_1_1") (pintype "bidirectional"))
      (node (ref "BAROMETER") (pin "7") (pinfunction "GND_2_7") (pintype "bidirectional"))
      (node (ref "C1") (pin "2") (pinfunction "2_2") (pintype "passive"))
      (node (ref "C10") (pin "2") (pinfunction "2_2") (pintype "passive"))
      (node (ref "C11") (pin "2") (pinfunction "2_2") (pintype "passive"))
      (node (ref "C12") (pin "2") (pinfunction "2_2") (pintype "passive"))
      (node (ref "C13") (pin "2") (pinfunction "2_2") (pintype "passive"))
      (node (ref "C14") (pin "2") (pinfunction "2_2") (pintype "passive"))
      (node (ref "C15") (pin "2") (pinfunction "2_2") (pintype "passive"))
      (node (ref "C16") (pin "2") (pinfunction "2_2") (pintype "passive"))
      (node (ref "C17") (pin "2") (pinfunction "2_2") (pintype "passive"))
      (node (ref "C18") (pin "2") (pinfunction "2_2") (pintype "passive"))
      (node (ref "C19") (pin "1") (pinfunction "1_1") (pintype "passive"))
      (node (ref "C2") (pin "2") (pinfunction "2_2") (pintype "passive"))
      (node (ref "C20") (pin "2") (pinfunction "2_2") (pintype "passive"))
      (node (ref "C21") (pin "2") (pinfunction "2_2") (pintype "passive"))
      (node (ref "C22") (pin "2") (pinfunction "2_2") (pintype "passive"))
      (node (ref "C23") (pin "2") (pinfunction "2_2") (pintype "passive"))
      (node (ref "C24") (pin "2") (pinfunction "2_2") (pintype "passive"))
      (node (ref "C25") (pin "1") (pinfunction "1_1") (pintype "passive"))
      (node (ref "C26") (pin "2") (pinfunction "2_2") (pintype "passive"))
      (node (ref "C27") (pin "2") (pinfunction "2_2") (pintype "passive"))
      (node (ref "C28") (pin "1") (pinfunction "1_1") (pintype "passive"))
      (node (ref "C29") (pin "1") (pinfunction "1_1") (pintype "passive"))
      (node (ref "C3") (pin "1") (pinfunction "1_1") (pintype "passive"))
      (node (ref "C4") (pin "2") (pinfunction "2_2") (pintype "passive"))
      (node (ref "C5") (pin "2") (pinfunction "2_2") (pintype "passive"))
      (node (ref "C6") (pin "2") (pinfunction "2_2") (pintype "passive"))
      (node (ref "C7") (pin "2") (pinfunction "2_2") (pintype "passive"))
      (node (ref "C8") (pin "2") (pinfunction "2_2") (pintype "passive"))
      (node (ref "C9") (pin "2") (pinfunction "2_2") (pintype "passive"))
      (node (ref "D1") (pin "C") (pinfunction "C_C") (pintype "passive"))
      (node (ref "GPS") (pin "1") (pinfunction "GND_1_1") (pintype "bidirectional"))
      (node (ref "GPS") (pin "10") (pinfunction "GND_5_10") (pintype "bidirectional"))
      (node (ref "GPS") (pin "11") (pinfunction "GND_6_11") (pintype "bidirectional"))
      (node (ref "GPS") (pin "15") (pinfunction "GND_7_15") (pintype "bidirectional"))
      (node (ref "GPS") (pin "16") (pinfunction "GND_8_16") (pintype "bidirectional"))
      (node (ref "GPS") (pin "20") (pinfunction "GND_9_20") (pintype "bidirectional"))
      (node (ref "GPS") (pin "4") (pinfunction "GND_2_4") (pintype "bidirectional"))
      (node (ref "GPS") (pin "5") (pinfunction "GND_3_5") (pintype "bidirectional"))
      (node (ref "GPS") (pin "6") (pinfunction "GND_4_6") (pintype "bidirectional"))
      (node (ref "IMU") (pin "4") (pinfunction "GNDA_4") (pintype "bidirectional"))
      (node (ref "IMU") (pin "6") (pinfunction "GNDIO_6") (pintype "bidirectional"))
      (node (ref "IMU") (pin "7") (pinfunction "PS_7") (pintype "bidirectional"))
      (node (ref "JP1") (pin "2") (pinfunction "2_2") (pintype "passive"))
      (node (ref "JP2") (pin "2") (pinfunction "2_2") (pintype "passive"))
      (node (ref "JST_CONNECTION") (pin "1") (pinfunction "1_1") (pintype "bidirectional"))
      (node (ref "MAGNETOMETER") (pin "6") (pinfunction "GND_1_6") (pintype "bidirectional"))
      (node (ref "MAGNETOMETER") (pin "8") (pinfunction "GND_2_8") (pintype "bidirectional"))
      (node (ref "MICROCONTROLLER") (pin "12") (pinfunction "VSSA/VREF-_12") (pintype "bidirectional"))
      (node (ref "MICROCONTROLLER") (pin "18") (pinfunction "VSS_1_18") (pintype "bidirectional"))
      (node (ref "MICROCONTROLLER") (pin "31") (pinfunction "VSS_2_31") (pintype "bidirectional"))
      (node (ref "MICROCONTROLLER") (pin "47") (pinfunction "VSS_3_47") (pintype "bidirectional"))
      (node (ref "MICROCONTROLLER") (pin "63") (pinfunction "VSS_4_63") (pintype "bidirectional"))
      (node (ref "POWER_MODULE") (pin "2") (pinfunction "GND_2") (pintype "power_in"))
      (node (ref "POWER_MODULE") (pin "7") (pinfunction "GND_7") (pintype "power_in"))
      (node (ref "R5") (pin "2") (pinfunction "2_2") (pintype "passive"))
      (node (ref "S2") (pin "3") (pinfunction "3_3") (pintype "passive"))
      (node (ref "S2") (pin "4") (pinfunction "4_4") (pintype "passive"))
      (node (ref "U1") (pin "9") (pinfunction "EPAD_9") (pintype "passive"))
      (node (ref "USB_COMM_MODE_FILTER") (pin "5") (pinfunction "GND_2_5") (pintype "passive"))
      (node (ref "USB_COMM_MODE_FILTER") (pin "8") (pinfunction "GND_8") (pintype "passive"))
      (node (ref "Y1") (pin "2") (pinfunction "GROUND_2") (pintype "bidirectional"))
    )
    (net (code "52") (name "Net-(BAROMETER-VDD)") (class "Default")
      (node (ref "BAROMETER") (pin "8") (pinfunction "VDD_8") (pintype "bidirectional"))
      (node (ref "C1") (pin "1") (pinfunction "1_1") (pintype "passive"))
      (node (ref "C26") (pin "1") (pinfunction "1_1") (pintype "passive"))
      (node (ref "L7") (pin "2") (pinfunction "2_2") (pintype "passive"))
    )
    (net (code "53") (name "Net-(D1-PadA)") (class "Default")
      (node (ref "D1") (pin "A") (pinfunction "A_A") (pintype "passive"))
      (node (ref "R3") (pin "1") (pinfunction "1_1") (pintype "passive"))
    )
    (net (code "54") (name "Net-(GPS-TIMEPULSE)") (class "Default")
      (node (ref "GPS") (pin "7") (pinfunction "TIMEPULSE_7") (pintype "bidirectional"))
      (node (ref "L4") (pin "2") (pinfunction "2_2") (pintype "passive"))
    )
    (net (code "55") (name "Net-(GPS-VCC)") (class "Default")
      (node (ref "C25") (pin "2") (pinfunction "2_2") (pintype "passive"))
      (node (ref "C28") (pin "2") (pinfunction "2_2") (pintype "passive"))
      (node (ref "GPS") (pin "17") (pinfunction "VCC_17") (pintype "bidirectional"))
      (node (ref "L6") (pin "1") (pinfunction "1_1") (pintype "passive"))
    )
    (net (code "56") (name "Net-(IMU-VDD)") (class "Default")
      (node (ref "C24") (pin "1") (pinfunction "1_1") (pintype "passive"))
      (node (ref "C4") (pin "1") (pinfunction "1_1") (pintype "passive"))
      (node (ref "IMU") (pin "3") (pinfunction "VDD_3") (pintype "bidirectional"))
      (node (ref "L3") (pin "1") (pinfunction "1_1") (pintype "passive"))
    )
    (net (code "57") (name "Net-(MAGNETOMETER-C1)") (class "Default")
      (node (ref "C13") (pin "1") (pinfunction "1_1") (pintype "passive"))
      (node (ref "MAGNETOMETER") (pin "5") (pinfunction "C1_5") (pintype "bidirectional"))
    )
    (net (code "58") (name "Net-(MAGNETOMETER-VDD)") (class "Default")
      (node (ref "C11") (pin "1") (pinfunction "1_1") (pintype "passive"))
      (node (ref "C12") (pin "1") (pinfunction "1_1") (pintype "passive"))
      (node (ref "C27") (pin "1") (pinfunction "1_1") (pintype "passive"))
      (node (ref "L8") (pin "1") (pinfunction "1_1") (pintype "passive"))
      (node (ref "MAGNETOMETER") (pin "9") (pinfunction "VDD_9") (pintype "bidirectional"))
    )
    (net (code "59") (name "Net-(MICROCONTROLLER-PC8)") (class "Default")
      (node (ref "MICROCONTROLLER") (pin "39") (pinfunction "PC8_39") (pintype "bidirectional"))
      (node (ref "R13") (pin "1") (pinfunction "1_1") (pintype "passive"))
    )
    (net (code "60") (name "Net-(MICROCONTROLLER-PC9)") (class "Default")
      (node (ref "MICROCONTROLLER") (pin "40") (pinfunction "PC9_40") (pintype "bidirectional"))
      (node (ref "R12") (pin "1") (pinfunction "1_1") (pintype "passive"))
    )
    (net (code "61") (name "Net-(Y1-OUTPUT)") (class "Default")
      (node (ref "R11") (pin "1") (pinfunction "1_1") (pintype "passive"))
      (node (ref "Y1") (pin "3") (pinfunction "OUTPUT_3") (pintype "bidirectional"))
    )
    (net (code "62") (name "unconnected-(AIRSPEED-NC_1-Pad6)") (class "Default")
      (node (ref "AIRSPEED") (pin "6") (pinfunction "NC_1_6") (pintype "bidirectional"))
    )
    (net (code "63") (name "unconnected-(AIRSPEED-NC_2-Pad7)") (class "Default")
      (node (ref "AIRSPEED") (pin "7") (pinfunction "NC_2_7") (pintype "bidirectional"))
    )
    (net (code "64") (name "unconnected-(AIRSPEED-NC_3-Pad8)") (class "Default")
      (node (ref "AIRSPEED") (pin "8") (pinfunction "NC_3_8") (pintype "bidirectional"))
    )
    (net (code "65") (name "unconnected-(GPS-EP-Pad21)") (class "Default")
      (node (ref "GPS") (pin "21") (pinfunction "EP_21") (pintype "bidirectional"))
    )
    (net (code "66") (name "unconnected-(GPS-EXTINT-Pad19)") (class "Default")
      (node (ref "GPS") (pin "19") (pinfunction "EXTINT_19") (pintype "bidirectional"))
    )
    (net (code "67") (name "unconnected-(GPS-SCL-Pad12)") (class "Default")
      (node (ref "GPS") (pin "12") (pinfunction "SCL_12") (pintype "bidirectional"))
    )
    (net (code "68") (name "unconnected-(GPS-SDA-Pad9)") (class "Default")
      (node (ref "GPS") (pin "9") (pinfunction "SDA_9") (pintype "bidirectional"))
    )
    (net (code "69") (name "unconnected-(IMU-NC-Pad2)") (class "Default")
      (node (ref "IMU") (pin "2") (pinfunction "NC_2") (pintype "no_connect"))
    )
    (net (code "70") (name "unconnected-(MAGNETOMETER-NC_1-Pad2)") (class "Default")
      (node (ref "MAGNETOMETER") (pin "2") (pinfunction "NC_1_2") (pintype "bidirectional"))
    )
    (net (code "71") (name "unconnected-(MAGNETOMETER-NC_2-Pad11)") (class "Default")
      (node (ref "MAGNETOMETER") (pin "11") (pinfunction "NC_2_11") (pintype "bidirectional"))
    )
    (net (code "72") (name "unconnected-(MAGNETOMETER-NC_3-Pad12)") (class "Default")
      (node (ref "MAGNETOMETER") (pin "12") (pinfunction "NC_3_12") (pintype "bidirectional"))
    )
    (net (code "73") (name "unconnected-(MICROCONTROLLER-PA2-Pad16)") (class "Default")
      (node (ref "MICROCONTROLLER") (pin "16") (pinfunction "PA2_16") (pintype "bidirectional"))
    )
    (net (code "74") (name "unconnected-(MICROCONTROLLER-PA3-Pad17)") (class "Default")
      (node (ref "MICROCONTROLLER") (pin "17") (pinfunction "PA3_17") (pintype "bidirectional"))
    )
    (net (code "75") (name "unconnected-(MICROCONTROLLER-PA8-Pad41)") (class "Default")
      (node (ref "MICROCONTROLLER") (pin "41") (pinfunction "PA8_41") (pintype "bidirectional"))
    )
    (net (code "76") (name "unconnected-(MICROCONTROLLER-PA9-Pad42)") (class "Default")
      (node (ref "MICROCONTROLLER") (pin "42") (pinfunction "PA9_42") (pintype "bidirectional"))
    )
    (net (code "77") (name "unconnected-(MICROCONTROLLER-PA10-Pad43)") (class "Default")
      (node (ref "MICROCONTROLLER") (pin "43") (pinfunction "PA10_43") (pintype "bidirectional"))
    )
    (net (code "78") (name "unconnected-(MICROCONTROLLER-PA15-Pad50)") (class "Default")
      (node (ref "MICROCONTROLLER") (pin "50") (pinfunction "PA15_50") (pintype "bidirectional"))
    )
    (net (code "79") (name "unconnected-(MICROCONTROLLER-PB0-Pad26)") (class "Default")
      (node (ref "MICROCONTROLLER") (pin "26") (pinfunction "PB0_26") (pintype "bidirectional"))
    )
    (net (code "80") (name "unconnected-(MICROCONTROLLER-PB1-Pad27)") (class "Default")
      (node (ref "MICROCONTROLLER") (pin "27") (pinfunction "PB1_27") (pintype "bidirectional"))
    )
    (net (code "81") (name "unconnected-(MICROCONTROLLER-PB4-Pad56)") (class "Default")
      (node (ref "MICROCONTROLLER") (pin "56") (pinfunction "PB4_56") (pintype "bidirectional"))
    )
    (net (code "82") (name "unconnected-(MICROCONTROLLER-PB5-Pad57)") (class "Default")
      (node (ref "MICROCONTROLLER") (pin "57") (pinfunction "PB5_57") (pintype "bidirectional"))
    )
    (net (code "83") (name "unconnected-(MICROCONTROLLER-PB12-Pad33)") (class "Default")
      (node (ref "MICROCONTROLLER") (pin "33") (pinfunction "PB12_33") (pintype "bidirectional"))
    )
    (net (code "84") (name "unconnected-(MICROCONTROLLER-PC2-Pad10)") (class "Default")
      (node (ref "MICROCONTROLLER") (pin "10") (pinfunction "PC2_10") (pintype "bidirectional"))
    )
    (net (code "85") (name "unconnected-(MICROCONTROLLER-PC4-Pad24)") (class "Default")
      (node (ref "MICROCONTROLLER") (pin "24") (pinfunction "PC4_24") (pintype "bidirectional"))
    )
    (net (code "86") (name "unconnected-(MICROCONTROLLER-PC5-Pad25)") (class "Default")
      (node (ref "MICROCONTROLLER") (pin "25") (pinfunction "PC5_25") (pintype "bidirectional"))
    )
    (net (code "87") (name "unconnected-(MICROCONTROLLER-PC6-Pad37)") (class "Default")
      (node (ref "MICROCONTROLLER") (pin "37") (pinfunction "PC6_37") (pintype "bidirectional"))
    )
    (net (code "88") (name "unconnected-(MICROCONTROLLER-PC7-Pad38)") (class "Default")
      (node (ref "MICROCONTROLLER") (pin "38") (pinfunction "PC7_38") (pintype "bidirectional"))
    )
    (net (code "89") (name "unconnected-(MICROCONTROLLER-PC12-Pad53)") (class "Default")
      (node (ref "MICROCONTROLLER") (pin "53") (pinfunction "PC12_53") (pintype "bidirectional"))
    )
    (net (code "90") (name "unconnected-(MICROCONTROLLER-PC13-Pad2)") (class "Default")
      (node (ref "MICROCONTROLLER") (pin "2") (pinfunction "PC13_2") (pintype "bidirectional"))
    )
    (net (code "91") (name "unconnected-(MICROCONTROLLER-PC14-OSC32_IN-Pad3)") (class "Default")
      (node (ref "MICROCONTROLLER") (pin "3") (pinfunction "PC14-OSC32_IN_3") (pintype "bidirectional"))
    )
    (net (code "92") (name "unconnected-(MICROCONTROLLER-PC15-OSC32_OUT-Pad4)") (class "Default")
      (node (ref "MICROCONTROLLER") (pin "4") (pinfunction "PC15-OSC32_OUT_4") (pintype "bidirectional"))
    )
    (net (code "93") (name "unconnected-(MICROCONTROLLER-PD2-Pad54)") (class "Default")
      (node (ref "MICROCONTROLLER") (pin "54") (pinfunction "PD2_54") (pintype "bidirectional"))
    )
    (net (code "94") (name "unconnected-(MICROCONTROLLER-PH1-OSC_OUT-Pad6)") (class "Default")
      (node (ref "MICROCONTROLLER") (pin "6") (pinfunction "PH1-OSC_OUT_6") (pintype "bidirectional"))
    )
    (net (code "95") (name "unconnected-(USB_COMM_MODE_FILTER-ID-Pad4)") (class "Default")
      (node (ref "USB_COMM_MODE_FILTER") (pin "4") (pinfunction "ID_4") (pintype "passive"))
    )
    (net (code "96") (name "unconnected-(Y1-TRI-STATE-Pad1)") (class "Default")
      (node (ref "Y1") (pin "1") (pinfunction "TRI-STATE_1") (pintype "bidirectional"))
    )
  )
)
